# MuscleMouse.net
KiCad netlist of a schematic drawn in EAGLE
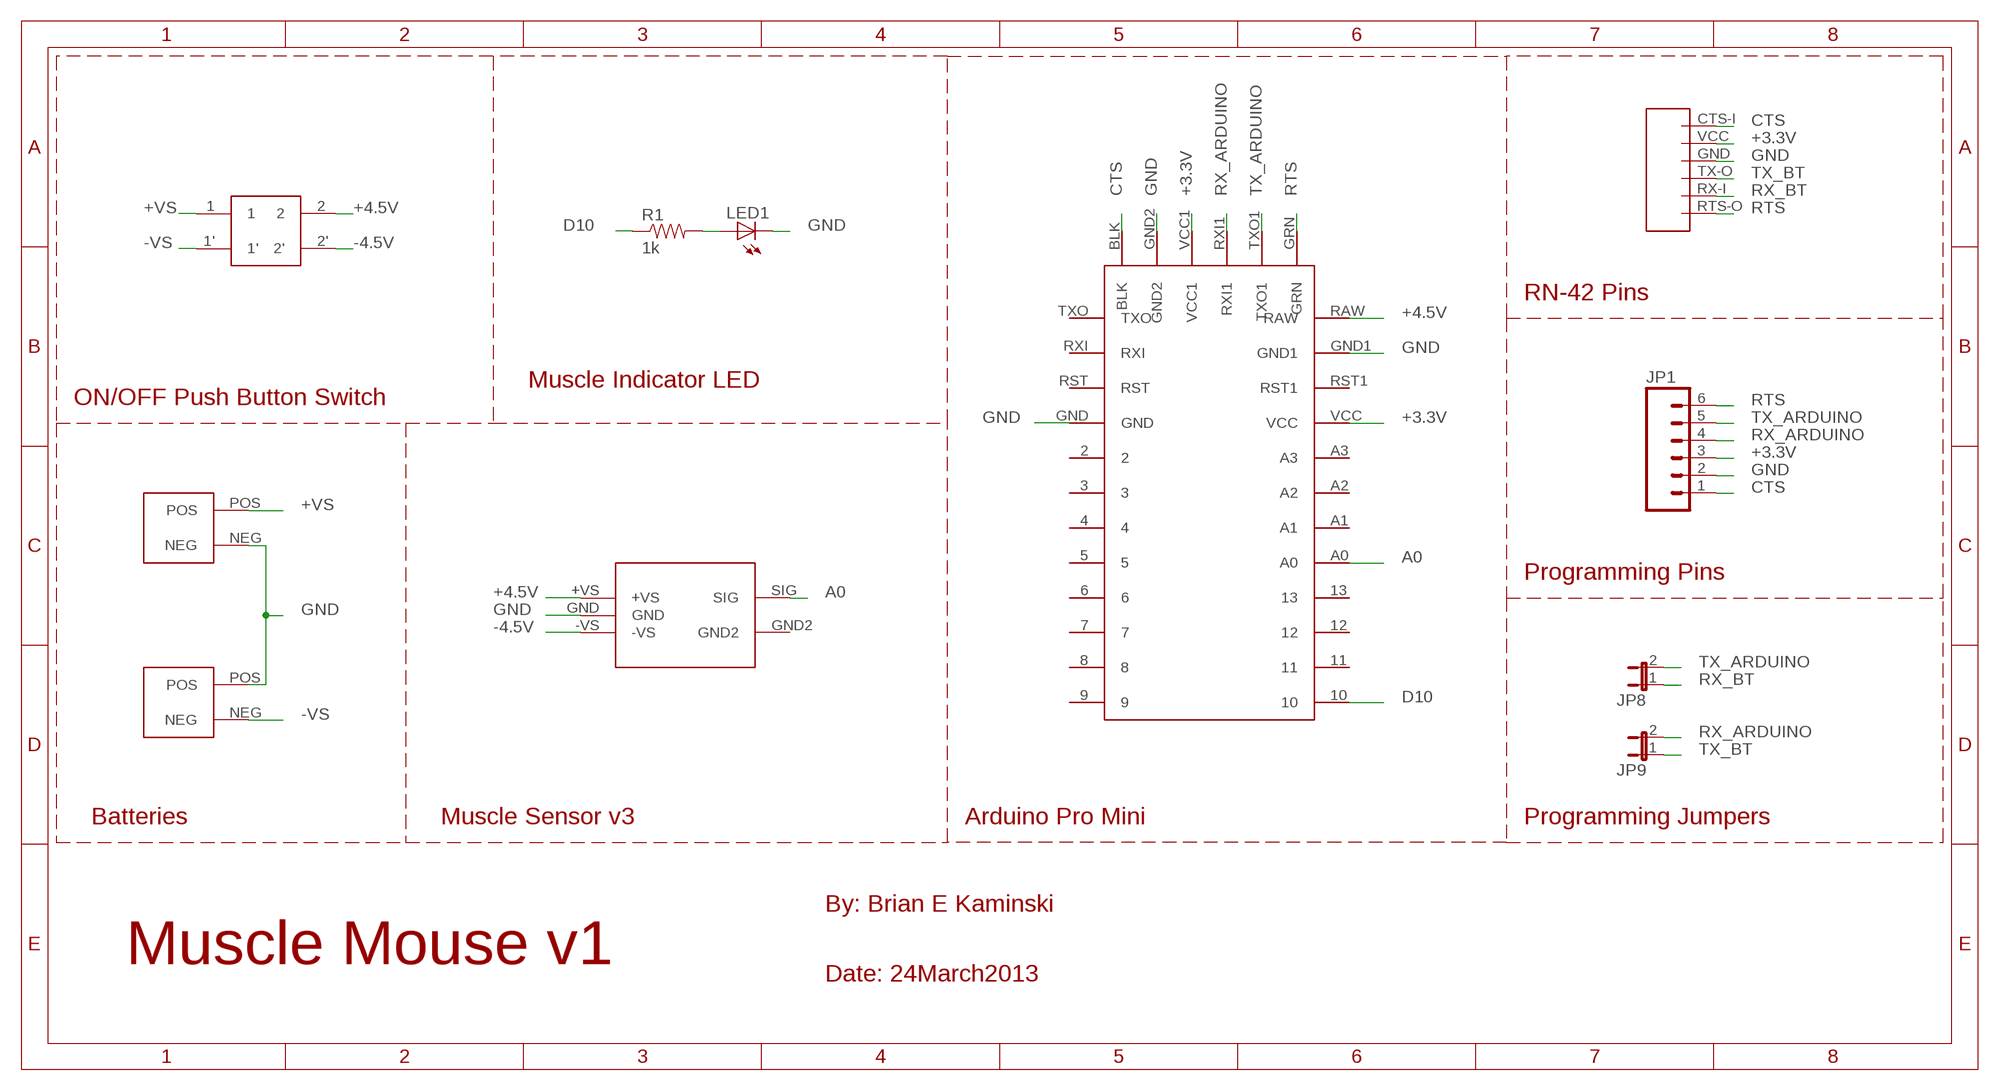
[diagram p0: schematic, sheet 1, part 1 of 2]
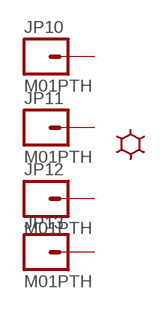
[diagram p1: schematic, sheet 1, part 2 of 2]

(export (version "E")
  (design (tool "Eeschema 10.0.6"))
  (components
    (comp (ref "JP1")
      (value "M06SIP")
      (footprint "eagle-import:1X06")
      (libsource (lib "eagle-import") (part "M06SIP"))
    )
    (comp (ref "JP8")
      (value "JUMPER-2SMD-NC")
      (footprint "eagle-import:SJ_2S")
      (libsource (lib "eagle-import") (part "JUMPER-2SMD-NC"))
    )
    (comp (ref "JP9")
      (value "JUMPER-2SMD-NC")
      (footprint "eagle-import:SJ_2S")
      (libsource (lib "eagle-import") (part "JUMPER-2SMD-NC"))
    )
    (comp (ref "JP10")
      (value "M01PTH")
      (footprint "eagle-import:1X01")
      (libsource (lib "eagle-import") (part "M01PTH"))
    )
    (comp (ref "JP11")
      (value "M01PTH")
      (footprint "eagle-import:1X01")
      (libsource (lib "eagle-import") (part "M01PTH"))
    )
    (comp (ref "JP12")
      (value "M01PTH")
      (footprint "eagle-import:1X01")
      (libsource (lib "eagle-import") (part "M01PTH"))
    )
    (comp (ref "JP13")
      (value "M01PTH")
      (footprint "eagle-import:1X01")
      (libsource (lib "eagle-import") (part "M01PTH"))
    )
    (comp (ref "LED1")
      (value "LED0603")
      (footprint "eagle-import:LED-0603")
      (libsource (lib "eagle-import") (part "LED0603"))
    )
    (comp (ref "R1")
      (value "1k")
      (footprint "eagle-import:1206")
      (libsource (lib "eagle-import") (part "RESISTOR1206"))
    )
    (comp (ref "U$1")
      (value "AAA_BATT_HOLDER_3STACK")
      (footprint "eagle-import:AAA_BATT_HOLDER_3STACK")
      (libsource (lib "eagle-import") (part "AAA_BATT_HOLDER_3STACK"))
    )
    (comp (ref "U$2")
      (value "AAA_BATT_HOLDER_3STACK")
      (footprint "eagle-import:AAA_BATT_HOLDER_3STACK")
      (libsource (lib "eagle-import") (part "AAA_BATT_HOLDER_3STACK"))
    )
    (comp (ref "U$3")
      (value "BLUESMIRF_HID")
      (footprint "eagle-import:BLUESMIRF_HID")
      (libsource (lib "eagle-import") (part "BLUESMIRF_HID"))
    )
    (comp (ref "U$4")
      (value "MUSCLE_SENSOR_V3")
      (footprint "eagle-import:MUSCLE_SENSOR_V3")
      (libsource (lib "eagle-import") (part "MUSCLE_SENSOR_V3"))
    )
    (comp (ref "U$5")
      (value "ARDUINO_PRO_MINI")
      (footprint "eagle-import:ARDUINO_PRO_MINI")
      (libsource (lib "eagle-import") (part "ARDUINO_PRO_MINI"))
    )
    (comp (ref "U$6")
      (value "ON_OFF_BUTTON")
      (footprint "eagle-import:ON_OFF_BUTTON")
      (libsource (lib "eagle-import") (part "ON_OFF_BUTTON"))
    )
    (comp (ref "U$7")
      (value "LOGOBIG")
      (footprint "eagle-import:LOGO_BIG")
      (libsource (lib "eagle-import") (part "LOGOBIG"))
    )
  )
  (nets
    (net (code "1") (name "/+3.3V") (class "Default")
      (node (ref "JP1") (pin "3") (pinfunction "3_3") (pintype "passive"))
      (node (ref "U$3") (pin "VCC") (pinfunction "VCC_VCC") (pintype "bidirectional"))
      (node (ref "U$5") (pin "VCC") (pinfunction "VCC_VCC") (pintype "bidirectional"))
      (node (ref "U$5") (pin "VCC1") (pinfunction "VCC1_VCC1") (pintype "bidirectional"))
    )
    (net (code "2") (name "/+4.5V") (class "Default")
      (node (ref "U$4") (pin "+VS") (pinfunction "+VS_+VS") (pintype "bidirectional"))
      (node (ref "U$5") (pin "RAW") (pinfunction "RAW_RAW") (pintype "bidirectional"))
      (node (ref "U$6") (pin "2") (pinfunction "2_2") (pintype "bidirectional"))
    )
    (net (code "3") (name "/+VS") (class "Default")
      (node (ref "U$1") (pin "POS") (pinfunction "POS_POS") (pintype "bidirectional"))
      (node (ref "U$6") (pin "1") (pinfunction "1_1") (pintype "bidirectional"))
    )
    (net (code "4") (name "/-4.5V") (class "Default")
      (node (ref "U$4") (pin "-VS") (pinfunction "-VS_-VS") (pintype "bidirectional"))
      (node (ref "U$6") (pin "2'") (pinfunction "2'_2'") (pintype "bidirectional"))
    )
    (net (code "5") (name "/-VS") (class "Default")
      (node (ref "U$2") (pin "NEG") (pinfunction "NEG_NEG") (pintype "bidirectional"))
      (node (ref "U$6") (pin "1'") (pinfunction "1'_1'") (pintype "bidirectional"))
    )
    (net (code "6") (name "/A0") (class "Default")
      (node (ref "U$4") (pin "SIG") (pinfunction "SIG_SIG") (pintype "bidirectional"))
      (node (ref "U$5") (pin "A0") (pinfunction "A0_A0") (pintype "bidirectional"))
    )
    (net (code "7") (name "/CTS") (class "Default")
      (node (ref "JP1") (pin "1") (pinfunction "1_1") (pintype "passive"))
      (node (ref "U$3") (pin "CTS-I") (pinfunction "CTS-I_CTS-I") (pintype "bidirectional"))
      (node (ref "U$5") (pin "BLK") (pinfunction "BLK_BLK") (pintype "bidirectional"))
    )
    (net (code "8") (name "/D10") (class "Default")
      (node (ref "R1") (pin "1") (pinfunction "1_1") (pintype "passive"))
      (node (ref "U$5") (pin "10") (pinfunction "10_10") (pintype "bidirectional"))
    )
    (net (code "9") (name "/GND") (class "Default")
      (node (ref "JP1") (pin "2") (pinfunction "2_2") (pintype "passive"))
      (node (ref "LED1") (pin "C") (pinfunction "C_C") (pintype "passive"))
      (node (ref "U$1") (pin "NEG") (pinfunction "NEG_NEG") (pintype "bidirectional"))
      (node (ref "U$2") (pin "POS") (pinfunction "POS_POS") (pintype "bidirectional"))
      (node (ref "U$3") (pin "GND") (pinfunction "GND_GND") (pintype "bidirectional"))
      (node (ref "U$4") (pin "GND") (pinfunction "GND_GND") (pintype "bidirectional"))
      (node (ref "U$5") (pin "GND") (pinfunction "GND_GND") (pintype "bidirectional"))
      (node (ref "U$5") (pin "GND1") (pinfunction "GND1_GND1") (pintype "bidirectional"))
      (node (ref "U$5") (pin "GND2") (pinfunction "GND2_GND2") (pintype "bidirectional"))
    )
    (net (code "10") (name "/RTS") (class "Default")
      (node (ref "JP1") (pin "6") (pinfunction "6_6") (pintype "passive"))
      (node (ref "U$3") (pin "RTS-O") (pinfunction "RTS-O_RTS-O") (pintype "bidirectional"))
      (node (ref "U$5") (pin "GRN") (pinfunction "GRN_GRN") (pintype "bidirectional"))
    )
    (net (code "11") (name "/RX_ARDUINO") (class "Default")
      (node (ref "JP1") (pin "4") (pinfunction "4_4") (pintype "passive"))
      (node (ref "JP9") (pin "2") (pinfunction "2_2") (pintype "passive"))
      (node (ref "U$5") (pin "RXI1") (pinfunction "RXI1_RXI1") (pintype "bidirectional"))
    )
    (net (code "12") (name "/RX_BT") (class "Default")
      (node (ref "JP8") (pin "1") (pinfunction "1_1") (pintype "passive"))
      (node (ref "U$3") (pin "RX-I") (pinfunction "RX-I_RX-I") (pintype "bidirectional"))
    )
    (net (code "13") (name "/TX_ARDUINO") (class "Default")
      (node (ref "JP1") (pin "5") (pinfunction "5_5") (pintype "passive"))
      (node (ref "JP8") (pin "2") (pinfunction "2_2") (pintype "passive"))
      (node (ref "U$5") (pin "TXO1") (pinfunction "TXO1_TXO1") (pintype "bidirectional"))
    )
    (net (code "14") (name "/TX_BT") (class "Default")
      (node (ref "JP9") (pin "1") (pinfunction "1_1") (pintype "passive"))
      (node (ref "U$3") (pin "TX-O") (pinfunction "TX-O_TX-O") (pintype "bidirectional"))
    )
    (net (code "15") (name "Net-(LED1-PadA)") (class "Default")
      (node (ref "LED1") (pin "A") (pinfunction "A_A") (pintype "passive"))
      (node (ref "R1") (pin "2") (pinfunction "2_2") (pintype "passive"))
    )
    (net (code "16") (name "unconnected-(JP10-Pad1)") (class "Default")
      (node (ref "JP10") (pin "1") (pinfunction "1_1") (pintype "passive"))
    )
    (net (code "17") (name "unconnected-(JP11-Pad1)") (class "Default")
      (node (ref "JP11") (pin "1") (pinfunction "1_1") (pintype "passive"))
    )
    (net (code "18") (name "unconnected-(JP12-Pad1)") (class "Default")
      (node (ref "JP12") (pin "1") (pinfunction "1_1") (pintype "passive"))
    )
    (net (code "19") (name "unconnected-(JP13-Pad1)") (class "Default")
      (node (ref "JP13") (pin "1") (pinfunction "1_1") (pintype "passive"))
    )
    (net (code "20") (name "unconnected-(U$4-PadGND2)") (class "Default")
      (node (ref "U$4") (pin "GND2") (pinfunction "GND2_GND2") (pintype "bidirectional"))
    )
    (net (code "21") (name "unconnected-(U$5-Pad2)") (class "Default")
      (node (ref "U$5") (pin "2") (pinfunction "2_2") (pintype "bidirectional"))
    )
    (net (code "22") (name "unconnected-(U$5-Pad3)") (class "Default")
      (node (ref "U$5") (pin "3") (pinfunction "3_3") (pintype "bidirectional"))
    )
    (net (code "23") (name "unconnected-(U$5-Pad4)") (class "Default")
      (node (ref "U$5") (pin "4") (pinfunction "4_4") (pintype "bidirectional"))
    )
    (net (code "24") (name "unconnected-(U$5-Pad5)") (class "Default")
      (node (ref "U$5") (pin "5") (pinfunction "5_5") (pintype "bidirectional"))
    )
    (net (code "25") (name "unconnected-(U$5-Pad6)") (class "Default")
      (node (ref "U$5") (pin "6") (pinfunction "6_6") (pintype "bidirectional"))
    )
    (net (code "26") (name "unconnected-(U$5-Pad7)") (class "Default")
      (node (ref "U$5") (pin "7") (pinfunction "7_7") (pintype "bidirectional"))
    )
    (net (code "27") (name "unconnected-(U$5-Pad8)") (class "Default")
      (node (ref "U$5") (pin "8") (pinfunction "8_8") (pintype "bidirectional"))
    )
    (net (code "28") (name "unconnected-(U$5-Pad9)") (class "Default")
      (node (ref "U$5") (pin "9") (pinfunction "9_9") (pintype "bidirectional"))
    )
    (net (code "29") (name "unconnected-(U$5-Pad11)") (class "Default")
      (node (ref "U$5") (pin "11") (pinfunction "11_11") (pintype "bidirectional"))
    )
    (net (code "30") (name "unconnected-(U$5-Pad12)") (class "Default")
      (node (ref "U$5") (pin "12") (pinfunction "12_12") (pintype "bidirectional"))
    )
    (net (code "31") (name "unconnected-(U$5-Pad13)") (class "Default")
      (node (ref "U$5") (pin "13") (pinfunction "13_13") (pintype "bidirectional"))
    )
    (net (code "32") (name "unconnected-(U$5-PadA1)") (class "Default")
      (node (ref "U$5") (pin "A1") (pinfunction "A1_A1") (pintype "bidirectional"))
    )
    (net (code "33") (name "unconnected-(U$5-PadA2)") (class "Default")
      (node (ref "U$5") (pin "A2") (pinfunction "A2_A2") (pintype "bidirectional"))
    )
    (net (code "34") (name "unconnected-(U$5-PadA3)") (class "Default")
      (node (ref "U$5") (pin "A3") (pinfunction "A3_A3") (pintype "bidirectional"))
    )
    (net (code "35") (name "unconnected-(U$5-PadRST)") (class "Default")
      (node (ref "U$5") (pin "RST") (pinfunction "RST_RST") (pintype "bidirectional"))
    )
    (net (code "36") (name "unconnected-(U$5-PadRST1)") (class "Default")
      (node (ref "U$5") (pin "RST1") (pinfunction "RST1_RST1") (pintype "bidirectional"))
    )
    (net (code "37") (name "unconnected-(U$5-PadRXI)") (class "Default")
      (node (ref "U$5") (pin "RXI") (pinfunction "RXI_RXI") (pintype "bidirectional"))
    )
    (net (code "38") (name "unconnected-(U$5-PadTXO)") (class "Default")
      (node (ref "U$5") (pin "TXO") (pinfunction "TXO_TXO") (pintype "bidirectional"))
    )
  )
)
